# mainBoard.net
KiCad netlist of a schematic drawn in EAGLE
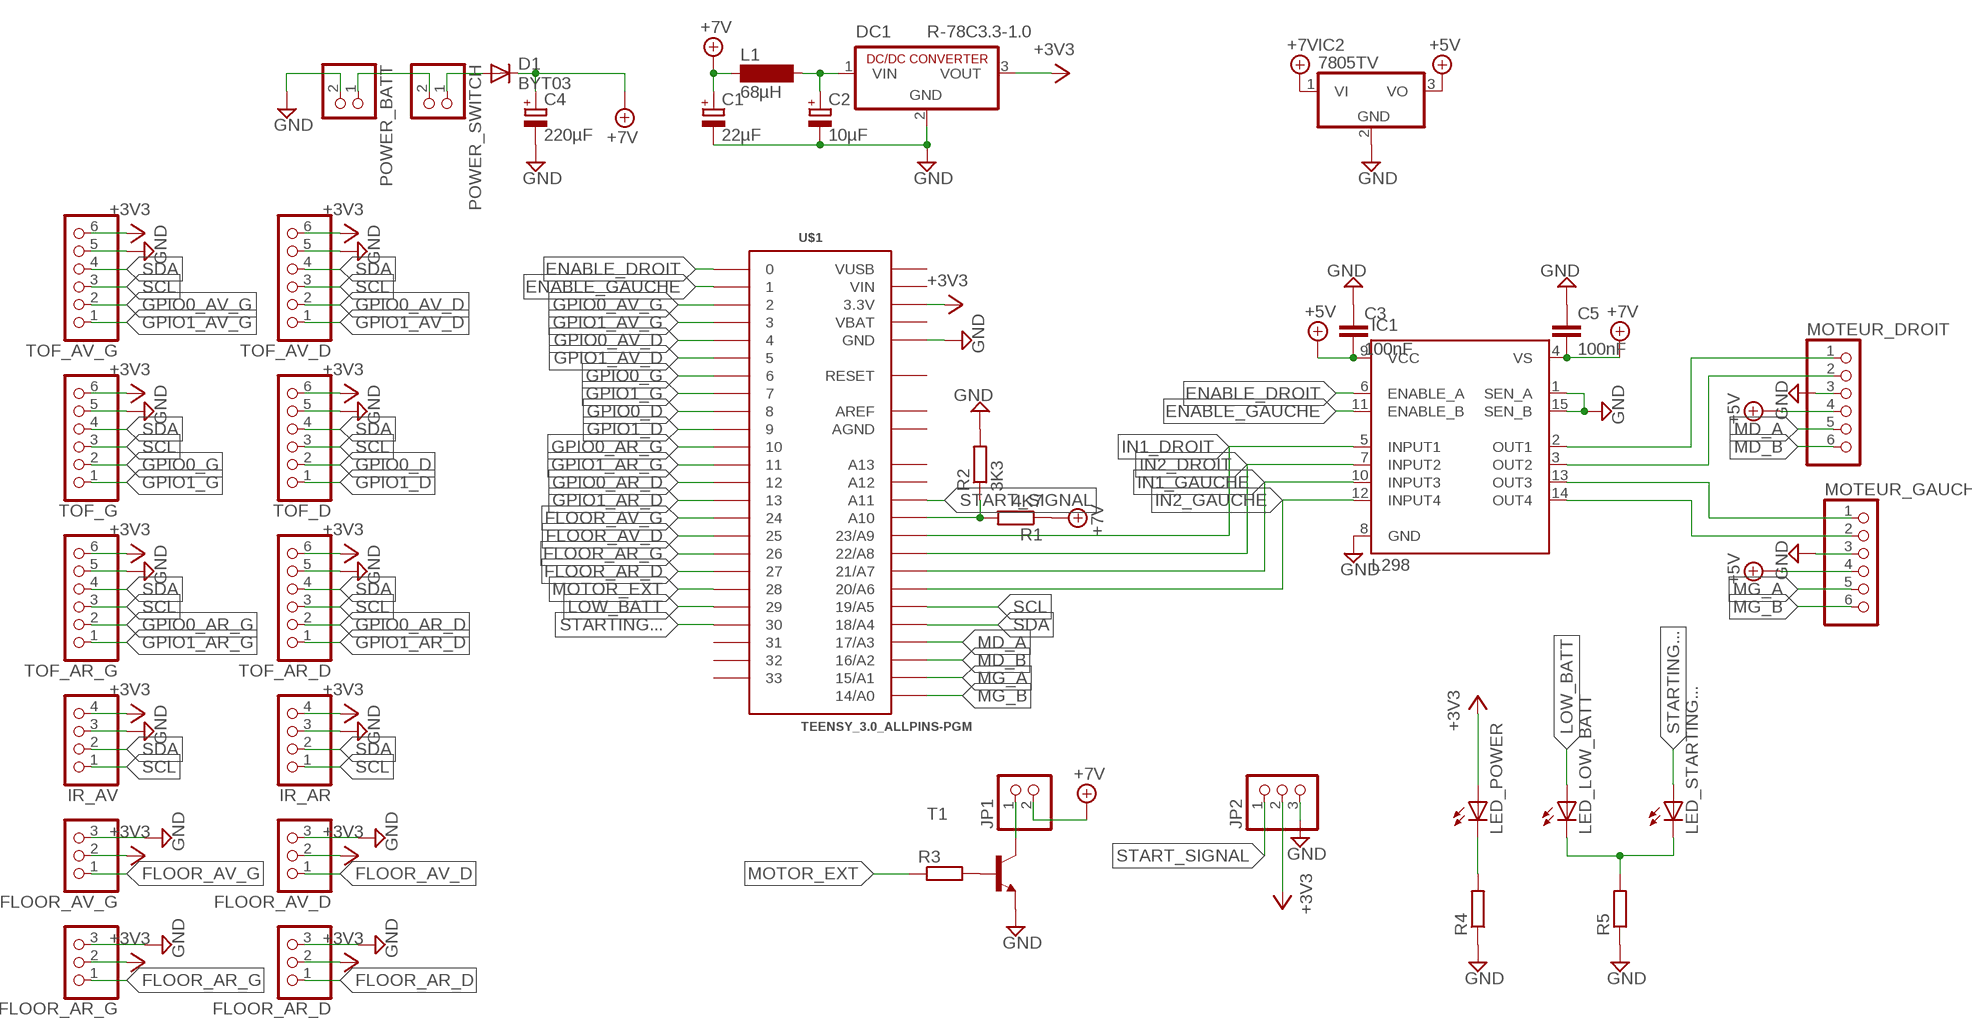
[diagram p0: schematic, sheet 1]

(export (version "E")
  (design (tool "Eeschema 10.0.6"))
  (components
    (comp (ref "C1")
      (value "22µF")
      (footprint "eagle-import:E2,5-6E")
      (libsource (lib "eagle-import") (part "CPOL-EUE2,5-6E"))
    )
    (comp (ref "C2")
      (value "10µF")
      (footprint "eagle-import:E2,5-6E")
      (libsource (lib "eagle-import") (part "CPOL-EUE2,5-6E"))
    )
    (comp (ref "C3")
      (value "100nF")
      (footprint "eagle-import:C050-024X044")
      (libsource (lib "eagle-import") (part "C-EU050-024X044"))
    )
    (comp (ref "C4")
      (value "220µF")
      (footprint "eagle-import:E2,5-7")
      (libsource (lib "eagle-import") (part "CPOL-EUE2.5-7"))
    )
    (comp (ref "C5")
      (value "100nF")
      (footprint "eagle-import:C050-024X044")
      (libsource (lib "eagle-import") (part "C-EU050-024X044"))
    )
    (comp (ref "D1")
      (value "BYT03")
      (footprint "eagle-import:DO27-15")
      (libsource (lib "eagle-import") (part "BYT03"))
    )
    (comp (ref "DC1")
      (value "R-78C3.3-1.0")
      (footprint "eagle-import:SIP3")
      (libsource (lib "eagle-import") (part "R-78C-1.03.3"))
    )
    (comp (ref "FLOOR_AR_D")
      (value "PINHD-1X3")
      (footprint "eagle-import:1X03")
      (libsource (lib "eagle-import") (part "PINHD-1X3"))
    )
    (comp (ref "FLOOR_AR_G")
      (value "PINHD-1X3")
      (footprint "eagle-import:1X03")
      (libsource (lib "eagle-import") (part "PINHD-1X3"))
    )
    (comp (ref "FLOOR_AV_D")
      (value "PINHD-1X3")
      (footprint "eagle-import:1X03")
      (libsource (lib "eagle-import") (part "PINHD-1X3"))
    )
    (comp (ref "FLOOR_AV_G")
      (value "PINHD-1X3")
      (footprint "eagle-import:1X03")
      (libsource (lib "eagle-import") (part "PINHD-1X3"))
    )
    (comp (ref "IC1")
      (value "L298")
      (footprint "eagle-import:MULTIWATT-15")
      (fields (field (name "MPN") "L298N"))
      (libsource (lib "eagle-import") (part "L298"))
    )
    (comp (ref "IC2")
      (value "7805TV")
      (footprint "eagle-import:TO220V")
      (libsource (lib "eagle-import") (part "78TV05"))
    )
    (comp (ref "IR_AR")
      (value "PINHD-1X4")
      (footprint "eagle-import:1X04")
      (libsource (lib "eagle-import") (part "PINHD-1X4"))
    )
    (comp (ref "IR_AV")
      (value "PINHD-1X4")
      (footprint "eagle-import:1X04")
      (libsource (lib "eagle-import") (part "PINHD-1X4"))
    )
    (comp (ref "JP1")
      (value "PINHD-1X2")
      (footprint "eagle-import:1X02")
      (libsource (lib "eagle-import") (part "PINHD-1X2"))
    )
    (comp (ref "JP2")
      (value "PINHD-1X3")
      (footprint "eagle-import:1X03")
      (libsource (lib "eagle-import") (part "PINHD-1X3"))
    )
    (comp (ref "L1")
      (value "68µH")
      (footprint "eagle-import:BS11")
      (libsource (lib "eagle-import") (part "BS11"))
    )
    (comp (ref "LED_LOW_BATT")
      (value "LED3MM")
      (footprint "eagle-import:LED3MM")
      (libsource (lib "eagle-import") (part "LED3MM"))
    )
    (comp (ref "LED_POWER")
      (value "LED3MM")
      (footprint "eagle-import:LED3MM")
      (libsource (lib "eagle-import") (part "LED3MM"))
    )
    (comp (ref "LED_STARTING...")
      (value "LED3MM")
      (footprint "eagle-import:LED3MM")
      (libsource (lib "eagle-import") (part "LED3MM"))
    )
    (comp (ref "MOTEUR_DROIT")
      (value "PINHD-1X6")
      (footprint "eagle-import:1X06")
      (libsource (lib "eagle-import") (part "PINHD-1X6"))
    )
    (comp (ref "MOTEUR_GAUCHE")
      (value "PINHD-1X6")
      (footprint "eagle-import:1X06")
      (libsource (lib "eagle-import") (part "PINHD-1X6"))
    )
    (comp (ref "POWER_BATT")
      (value "PINHD-1X2")
      (footprint "eagle-import:1X02")
      (libsource (lib "eagle-import") (part "PINHD-1X2"))
    )
    (comp (ref "POWER_SWITCH")
      (value "PINHD-1X2")
      (footprint "eagle-import:1X02")
      (libsource (lib "eagle-import") (part "PINHD-1X2"))
    )
    (comp (ref "R1")
      (value "4K7")
      (footprint "eagle-import:0204_7")
      (libsource (lib "eagle-import") (part "R-EU_0204/7"))
    )
    (comp (ref "R2")
      (value "3K3")
      (footprint "eagle-import:0204_7")
      (libsource (lib "eagle-import") (part "R-EU_0204/7"))
    )
    (comp (ref "R3")
      (value "R-EU_0204/7")
      (footprint "eagle-import:0204_7")
      (libsource (lib "eagle-import") (part "R-EU_0204/7"))
    )
    (comp (ref "R4")
      (value "R-EU_0204/7")
      (footprint "eagle-import:0204_7")
      (libsource (lib "eagle-import") (part "R-EU_0204/7"))
    )
    (comp (ref "R5")
      (value "R-EU_0207/2V")
      (footprint "eagle-import:0207_2V")
      (libsource (lib "eagle-import") (part "R-EU_0207/2V"))
    )
    (comp (ref "T1")
      (value "2N4124-NPN-TO92-CBE")
      (footprint "eagle-import:TO92-CBE")
      (libsource (lib "eagle-import") (part "-NPN-TO92-CBE2N4124"))
    )
    (comp (ref "TOF_AR_D")
      (value "PINHD-1X6")
      (footprint "eagle-import:1X06")
      (libsource (lib "eagle-import") (part "PINHD-1X6"))
    )
    (comp (ref "TOF_AR_G")
      (value "PINHD-1X6")
      (footprint "eagle-import:1X06")
      (libsource (lib "eagle-import") (part "PINHD-1X6"))
    )
    (comp (ref "TOF_AV_D")
      (value "PINHD-1X6")
      (footprint "eagle-import:1X06")
      (libsource (lib "eagle-import") (part "PINHD-1X6"))
    )
    (comp (ref "TOF_AV_G")
      (value "PINHD-1X6")
      (footprint "eagle-import:1X06")
      (libsource (lib "eagle-import") (part "PINHD-1X6"))
    )
    (comp (ref "TOF_D")
      (value "PINHD-1X6")
      (footprint "eagle-import:1X06")
      (libsource (lib "eagle-import") (part "PINHD-1X6"))
    )
    (comp (ref "TOF_G")
      (value "PINHD-1X6")
      (footprint "eagle-import:1X06")
      (libsource (lib "eagle-import") (part "PINHD-1X6"))
    )
    (comp (ref "U$1")
      (value "TEENSY_3.0_ALLPINS-PGM")
      (footprint "eagle-import:TEENSY_3.0_ALLPINS-PGM")
      (libsource (lib "eagle-import") (part "TEENSY_3.0_ALLPINS-PGM"))
    )
  )
  (nets
    (net (code "1") (name "+3V3") (class "Default")
      (node (ref "DC1") (pin "3") (pinfunction "VOUT_3") (pintype "passive"))
      (node (ref "FLOOR_AR_D") (pin "2") (pinfunction "2_2") (pintype "passive"))
      (node (ref "FLOOR_AR_G") (pin "2") (pinfunction "2_2") (pintype "passive"))
      (node (ref "FLOOR_AV_D") (pin "2") (pinfunction "2_2") (pintype "passive"))
      (node (ref "FLOOR_AV_G") (pin "2") (pinfunction "2_2") (pintype "passive"))
      (node (ref "IR_AR") (pin "4") (pinfunction "4_4") (pintype "passive"))
      (node (ref "IR_AV") (pin "4") (pinfunction "4_4") (pintype "passive"))
      (node (ref "JP2") (pin "2") (pinfunction "2_2") (pintype "passive"))
      (node (ref "LED_POWER") (pin "A") (pinfunction "A_A") (pintype "passive"))
      (node (ref "TOF_AR_D") (pin "6") (pinfunction "6_6") (pintype "passive"))
      (node (ref "TOF_AR_G") (pin "6") (pinfunction "6_6") (pintype "passive"))
      (node (ref "TOF_AV_D") (pin "6") (pinfunction "6_6") (pintype "passive"))
      (node (ref "TOF_AV_G") (pin "6") (pinfunction "6_6") (pintype "passive"))
      (node (ref "TOF_D") (pin "6") (pinfunction "6_6") (pintype "passive"))
      (node (ref "TOF_G") (pin "6") (pinfunction "6_6") (pintype "passive"))
      (node (ref "U$1") (pin "3.3V") (pinfunction "3.3V_3.3V") (pintype "power_in"))
      (node (ref "U$1") (pin "3.3V1") (pinfunction "3.3V_3.3V1") (pintype "power_in"))
      (node (ref "U$1") (pin "3.3V2") (pinfunction "3.3V_3.3V2") (pintype "power_in"))
    )
    (net (code "2") (name "+5V") (class "Default")
      (node (ref "C3") (pin "2") (pinfunction "2_2") (pintype "passive"))
      (node (ref "IC1") (pin "9") (pinfunction "VCC_9") (pintype "power_in"))
      (node (ref "IC2") (pin "3") (pinfunction "VO_3") (pintype "passive"))
      (node (ref "MOTEUR_DROIT") (pin "4") (pinfunction "4_4") (pintype "passive"))
      (node (ref "MOTEUR_GAUCHE") (pin "4") (pinfunction "4_4") (pintype "passive"))
    )
    (net (code "3") (name "+7V") (class "Default")
      (node (ref "C1") (pin "+") (pinfunction "+_+") (pintype "passive"))
      (node (ref "C4") (pin "+") (pinfunction "+_+") (pintype "passive"))
      (node (ref "C5") (pin "2") (pinfunction "2_2") (pintype "passive"))
      (node (ref "D1") (pin "C") (pinfunction "C_C") (pintype "passive"))
      (node (ref "IC1") (pin "4") (pinfunction "VS_4") (pintype "power_in"))
      (node (ref "IC2") (pin "1") (pinfunction "VI_1") (pintype "input"))
      (node (ref "JP1") (pin "2") (pinfunction "2_2") (pintype "passive"))
      (node (ref "L1") (pin "1") (pinfunction "1_1") (pintype "passive"))
      (node (ref "R1") (pin "1") (pinfunction "1_1") (pintype "passive"))
    )
    (net (code "4") (name "/AGND") (class "Default")
      (node (ref "U$1") (pin "AGND") (pinfunction "AGND_AGND") (pintype "power_in"))
    )
    (net (code "5") (name "/AREF") (class "Default")
      (node (ref "U$1") (pin "AREF") (pinfunction "AREF_AREF") (pintype "power_in"))
    )
    (net (code "6") (name "/VBAT") (class "Default")
      (node (ref "U$1") (pin "VBAT") (pinfunction "VBAT_VBAT") (pintype "power_in"))
    )
    (net (code "7") (name "/VIN") (class "Default")
      (node (ref "U$1") (pin "VIN") (pinfunction "VIN_VIN") (pintype "power_in"))
    )
    (net (code "8") (name "/VUSB") (class "Default")
      (node (ref "U$1") (pin "VUSB") (pinfunction "VUSB_VUSB") (pintype "power_in"))
    )
    (net (code "9") (name "ENABLE_DROIT") (class "Default")
      (node (ref "IC1") (pin "6") (pinfunction "ENABLE_A_6") (pintype "input"))
      (node (ref "U$1") (pin "0") (pinfunction "0_0") (pintype "bidirectional"))
    )
    (net (code "10") (name "ENABLE_GAUCHE") (class "Default")
      (node (ref "IC1") (pin "11") (pinfunction "ENABLE_B_11") (pintype "input"))
      (node (ref "U$1") (pin "1") (pinfunction "1_1") (pintype "bidirectional"))
    )
    (net (code "11") (name "FLOOR_AR_D") (class "Default")
      (node (ref "FLOOR_AR_D") (pin "1") (pinfunction "1_1") (pintype "passive"))
      (node (ref "U$1") (pin "27") (pinfunction "27_27") (pintype "bidirectional"))
    )
    (net (code "12") (name "FLOOR_AR_G") (class "Default")
      (node (ref "FLOOR_AR_G") (pin "1") (pinfunction "1_1") (pintype "passive"))
      (node (ref "U$1") (pin "26") (pinfunction "26_26") (pintype "bidirectional"))
    )
    (net (code "13") (name "FLOOR_AV_D") (class "Default")
      (node (ref "FLOOR_AV_D") (pin "1") (pinfunction "1_1") (pintype "passive"))
      (node (ref "U$1") (pin "25") (pinfunction "25_25") (pintype "bidirectional"))
    )
    (net (code "14") (name "FLOOR_AV_G") (class "Default")
      (node (ref "FLOOR_AV_G") (pin "1") (pinfunction "1_1") (pintype "passive"))
      (node (ref "U$1") (pin "24") (pinfunction "24_24") (pintype "bidirectional"))
    )
    (net (code "15") (name "GND") (class "Default")
      (node (ref "C1") (pin "-") (pinfunction "-_-") (pintype "passive"))
      (node (ref "C2") (pin "-") (pinfunction "-_-") (pintype "passive"))
      (node (ref "C3") (pin "1") (pinfunction "1_1") (pintype "passive"))
      (node (ref "C4") (pin "-") (pinfunction "-_-") (pintype "passive"))
      (node (ref "C5") (pin "1") (pinfunction "1_1") (pintype "passive"))
      (node (ref "DC1") (pin "2") (pinfunction "GND_2") (pintype "passive"))
      (node (ref "FLOOR_AR_D") (pin "3") (pinfunction "3_3") (pintype "passive"))
      (node (ref "FLOOR_AR_G") (pin "3") (pinfunction "3_3") (pintype "passive"))
      (node (ref "FLOOR_AV_D") (pin "3") (pinfunction "3_3") (pintype "passive"))
      (node (ref "FLOOR_AV_G") (pin "3") (pinfunction "3_3") (pintype "passive"))
      (node (ref "IC1") (pin "1") (pinfunction "SEN_A_1") (pintype "input"))
      (node (ref "IC1") (pin "15") (pinfunction "SEN_B_15") (pintype "input"))
      (node (ref "IC1") (pin "8") (pinfunction "GND_8") (pintype "power_in"))
      (node (ref "IC2") (pin "2") (pinfunction "GND_2") (pintype "passive"))
      (node (ref "IR_AR") (pin "3") (pinfunction "3_3") (pintype "passive"))
      (node (ref "IR_AV") (pin "3") (pinfunction "3_3") (pintype "passive"))
      (node (ref "JP2") (pin "3") (pinfunction "3_3") (pintype "passive"))
      (node (ref "MOTEUR_DROIT") (pin "3") (pinfunction "3_3") (pintype "passive"))
      (node (ref "MOTEUR_GAUCHE") (pin "3") (pinfunction "3_3") (pintype "passive"))
      (node (ref "POWER_BATT") (pin "2") (pinfunction "2_2") (pintype "passive"))
      (node (ref "R2") (pin "2") (pinfunction "2_2") (pintype "passive"))
      (node (ref "R4") (pin "1") (pinfunction "1_1") (pintype "passive"))
      (node (ref "R5") (pin "1") (pinfunction "1_1") (pintype "passive"))
      (node (ref "T1") (pin "E") (pinfunction "E_E") (pintype "passive"))
      (node (ref "TOF_AR_D") (pin "5") (pinfunction "5_5") (pintype "passive"))
      (node (ref "TOF_AR_G") (pin "5") (pinfunction "5_5") (pintype "passive"))
      (node (ref "TOF_AV_D") (pin "5") (pinfunction "5_5") (pintype "passive"))
      (node (ref "TOF_AV_G") (pin "5") (pinfunction "5_5") (pintype "passive"))
      (node (ref "TOF_D") (pin "5") (pinfunction "5_5") (pintype "passive"))
      (node (ref "TOF_G") (pin "5") (pinfunction "5_5") (pintype "passive"))
      (node (ref "U$1") (pin "GND") (pinfunction "GND_GND") (pintype "power_in"))
      (node (ref "U$1") (pin "GND1") (pinfunction "GND_GND1") (pintype "power_in"))
      (node (ref "U$1") (pin "GND2") (pinfunction "GND_GND2") (pintype "power_in"))
    )
    (net (code "16") (name "GPIO0_AR_D") (class "Default")
      (node (ref "TOF_AR_D") (pin "2") (pinfunction "2_2") (pintype "passive"))
      (node (ref "U$1") (pin "12") (pinfunction "12_12") (pintype "bidirectional"))
    )
    (net (code "17") (name "GPIO0_AR_G") (class "Default")
      (node (ref "TOF_AR_G") (pin "2") (pinfunction "2_2") (pintype "passive"))
      (node (ref "U$1") (pin "10") (pinfunction "10_10") (pintype "bidirectional"))
    )
    (net (code "18") (name "GPIO0_AV_D") (class "Default")
      (node (ref "TOF_AV_D") (pin "2") (pinfunction "2_2") (pintype "passive"))
      (node (ref "U$1") (pin "4") (pinfunction "4_4") (pintype "bidirectional"))
    )
    (net (code "19") (name "GPIO0_AV_G") (class "Default")
      (node (ref "TOF_AV_G") (pin "2") (pinfunction "2_2") (pintype "passive"))
      (node (ref "U$1") (pin "2") (pinfunction "2_2") (pintype "bidirectional"))
    )
    (net (code "20") (name "GPIO0_D") (class "Default")
      (node (ref "TOF_D") (pin "2") (pinfunction "2_2") (pintype "passive"))
      (node (ref "U$1") (pin "8") (pinfunction "8_8") (pintype "bidirectional"))
    )
    (net (code "21") (name "GPIO0_G") (class "Default")
      (node (ref "TOF_G") (pin "2") (pinfunction "2_2") (pintype "passive"))
      (node (ref "U$1") (pin "6") (pinfunction "6_6") (pintype "bidirectional"))
    )
    (net (code "22") (name "GPIO1_AR_D") (class "Default")
      (node (ref "TOF_AR_D") (pin "1") (pinfunction "1_1") (pintype "passive"))
      (node (ref "U$1") (pin "13") (pinfunction "13_13") (pintype "bidirectional"))
    )
    (net (code "23") (name "GPIO1_AR_G") (class "Default")
      (node (ref "TOF_AR_G") (pin "1") (pinfunction "1_1") (pintype "passive"))
      (node (ref "U$1") (pin "11") (pinfunction "11_11") (pintype "bidirectional"))
    )
    (net (code "24") (name "GPIO1_AV_D") (class "Default")
      (node (ref "TOF_AV_D") (pin "1") (pinfunction "1_1") (pintype "passive"))
      (node (ref "U$1") (pin "5") (pinfunction "5_5") (pintype "bidirectional"))
    )
    (net (code "25") (name "GPIO1_AV_G") (class "Default")
      (node (ref "TOF_AV_G") (pin "1") (pinfunction "1_1") (pintype "passive"))
      (node (ref "U$1") (pin "3") (pinfunction "3_3") (pintype "bidirectional"))
    )
    (net (code "26") (name "GPIO1_D") (class "Default")
      (node (ref "TOF_D") (pin "1") (pinfunction "1_1") (pintype "passive"))
      (node (ref "U$1") (pin "9") (pinfunction "9_9") (pintype "bidirectional"))
    )
    (net (code "27") (name "GPIO1_G") (class "Default")
      (node (ref "TOF_G") (pin "1") (pinfunction "1_1") (pintype "passive"))
      (node (ref "U$1") (pin "7") (pinfunction "7_7") (pintype "bidirectional"))
    )
    (net (code "28") (name "IN1_DROIT") (class "Default")
      (node (ref "IC1") (pin "5") (pinfunction "INPUT1_5") (pintype "input"))
      (node (ref "U$1") (pin "23/A9") (pinfunction "23/A9_23/A9") (pintype "bidirectional"))
    )
    (net (code "29") (name "IN1_GAUCHE") (class "Default")
      (node (ref "IC1") (pin "10") (pinfunction "INPUT3_10") (pintype "input"))
      (node (ref "U$1") (pin "21/A7") (pinfunction "21/A7_21/A7") (pintype "bidirectional"))
    )
    (net (code "30") (name "IN2_DROIT") (class "Default")
      (node (ref "IC1") (pin "7") (pinfunction "INPUT2_7") (pintype "input"))
      (node (ref "U$1") (pin "22/A8") (pinfunction "22/A8_22/A8") (pintype "bidirectional"))
    )
    (net (code "31") (name "IN2_GAUCHE") (class "Default")
      (node (ref "IC1") (pin "12") (pinfunction "INPUT4_12") (pintype "input"))
      (node (ref "U$1") (pin "20/A6") (pinfunction "20/A6_20/A6") (pintype "bidirectional"))
    )
    (net (code "32") (name "LOW_BATT") (class "Default")
      (node (ref "LED_LOW_BATT") (pin "A") (pinfunction "A_A") (pintype "passive"))
      (node (ref "U$1") (pin "29") (pinfunction "29_29") (pintype "bidirectional"))
    )
    (net (code "33") (name "MD_A") (class "Default")
      (node (ref "MOTEUR_DROIT") (pin "5") (pinfunction "5_5") (pintype "passive"))
      (node (ref "U$1") (pin "17/A3") (pinfunction "17/A3_17/A3") (pintype "bidirectional"))
    )
    (net (code "34") (name "MD_B") (class "Default")
      (node (ref "MOTEUR_DROIT") (pin "6") (pinfunction "6_6") (pintype "passive"))
      (node (ref "U$1") (pin "16/A2") (pinfunction "16/A2_16/A2") (pintype "bidirectional"))
    )
    (net (code "35") (name "MG_A") (class "Default")
      (node (ref "MOTEUR_GAUCHE") (pin "5") (pinfunction "5_5") (pintype "passive"))
      (node (ref "U$1") (pin "15/A1") (pinfunction "15/A1_15/A1") (pintype "bidirectional"))
    )
    (net (code "36") (name "MG_B") (class "Default")
      (node (ref "MOTEUR_GAUCHE") (pin "6") (pinfunction "6_6") (pintype "passive"))
      (node (ref "U$1") (pin "14/A0") (pinfunction "14/A0_14/A0") (pintype "bidirectional"))
    )
    (net (code "37") (name "MOTOR_EXT") (class "Default")
      (node (ref "R3") (pin "1") (pinfunction "1_1") (pintype "passive"))
      (node (ref "U$1") (pin "28") (pinfunction "28_28") (pintype "bidirectional"))
    )
    (net (code "38") (name "Net-(D1-PadA)") (class "Default")
      (node (ref "D1") (pin "A") (pinfunction "A_A") (pintype "passive"))
      (node (ref "POWER_SWITCH") (pin "1") (pinfunction "1_1") (pintype "passive"))
    )
    (net (code "39") (name "Net-(DC1-VIN)") (class "Default")
      (node (ref "C2") (pin "+") (pinfunction "+_+") (pintype "passive"))
      (node (ref "DC1") (pin "1") (pinfunction "VIN_1") (pintype "passive"))
      (node (ref "L1") (pin "2") (pinfunction "2_2") (pintype "passive"))
    )
    (net (code "40") (name "Net-(IC1-OUT1)") (class "Default")
      (node (ref "IC1") (pin "2") (pinfunction "OUT1_2") (pintype "output"))
      (node (ref "MOTEUR_DROIT") (pin "1") (pinfunction "1_1") (pintype "passive"))
    )
    (net (code "41") (name "Net-(IC1-OUT2)") (class "Default")
      (node (ref "IC1") (pin "3") (pinfunction "OUT2_3") (pintype "output"))
      (node (ref "MOTEUR_DROIT") (pin "2") (pinfunction "2_2") (pintype "passive"))
    )
    (net (code "42") (name "Net-(IC1-OUT3)") (class "Default")
      (node (ref "IC1") (pin "13") (pinfunction "OUT3_13") (pintype "output"))
      (node (ref "MOTEUR_GAUCHE") (pin "1") (pinfunction "1_1") (pintype "passive"))
    )
    (net (code "43") (name "Net-(IC1-OUT4)") (class "Default")
      (node (ref "IC1") (pin "14") (pinfunction "OUT4_14") (pintype "output"))
      (node (ref "MOTEUR_GAUCHE") (pin "2") (pinfunction "2_2") (pintype "passive"))
    )
    (net (code "44") (name "Net-(JP1-Pad1)") (class "Default")
      (node (ref "JP1") (pin "1") (pinfunction "1_1") (pintype "passive"))
      (node (ref "T1") (pin "C") (pinfunction "C_C") (pintype "passive"))
    )
    (net (code "45") (name "Net-(LED_LOW_BATT-C)") (class "Default")
      (node (ref "LED_LOW_BATT") (pin "K") (pinfunction "C_K") (pintype "passive"))
      (node (ref "LED_STARTING...") (pin "K") (pinfunction "C_K") (pintype "passive"))
      (node (ref "R5") (pin "2") (pinfunction "2_2") (pintype "passive"))
    )
    (net (code "46") (name "Net-(LED_POWER-C)") (class "Default")
      (node (ref "LED_POWER") (pin "K") (pinfunction "C_K") (pintype "passive"))
      (node (ref "R4") (pin "2") (pinfunction "2_2") (pintype "passive"))
    )
    (net (code "47") (name "Net-(POWER_BATT-Pad1)") (class "Default")
      (node (ref "POWER_BATT") (pin "1") (pinfunction "1_1") (pintype "passive"))
      (node (ref "POWER_SWITCH") (pin "2") (pinfunction "2_2") (pintype "passive"))
    )
    (net (code "48") (name "Net-(R1-Pad2)") (class "Default")
      (node (ref "R1") (pin "2") (pinfunction "2_2") (pintype "passive"))
      (node (ref "R2") (pin "1") (pinfunction "1_1") (pintype "passive"))
      (node (ref "U$1") (pin "A10") (pinfunction "A10_A10") (pintype "bidirectional"))
    )
    (net (code "49") (name "Net-(R3-Pad2)") (class "Default")
      (node (ref "R3") (pin "2") (pinfunction "2_2") (pintype "passive"))
      (node (ref "T1") (pin "B") (pinfunction "B_B") (pintype "passive"))
    )
    (net (code "50") (name "SCL") (class "Default")
      (node (ref "IR_AR") (pin "1") (pinfunction "1_1") (pintype "passive"))
      (node (ref "IR_AV") (pin "1") (pinfunction "1_1") (pintype "passive"))
      (node (ref "TOF_AR_D") (pin "3") (pinfunction "3_3") (pintype "passive"))
      (node (ref "TOF_AR_G") (pin "3") (pinfunction "3_3") (pintype "passive"))
      (node (ref "TOF_AV_D") (pin "3") (pinfunction "3_3") (pintype "passive"))
      (node (ref "TOF_AV_G") (pin "3") (pinfunction "3_3") (pintype "passive"))
      (node (ref "TOF_D") (pin "3") (pinfunction "3_3") (pintype "passive"))
      (node (ref "TOF_G") (pin "3") (pinfunction "3_3") (pintype "passive"))
      (node (ref "U$1") (pin "19/A5") (pinfunction "19/A5_19/A5") (pintype "bidirectional"))
    )
    (net (code "51") (name "SDA") (class "Default")
      (node (ref "IR_AR") (pin "2") (pinfunction "2_2") (pintype "passive"))
      (node (ref "IR_AV") (pin "2") (pinfunction "2_2") (pintype "passive"))
      (node (ref "TOF_AR_D") (pin "4") (pinfunction "4_4") (pintype "passive"))
      (node (ref "TOF_AR_G") (pin "4") (pinfunction "4_4") (pintype "passive"))
      (node (ref "TOF_AV_D") (pin "4") (pinfunction "4_4") (pintype "passive"))
      (node (ref "TOF_AV_G") (pin "4") (pinfunction "4_4") (pintype "passive"))
      (node (ref "TOF_D") (pin "4") (pinfunction "4_4") (pintype "passive"))
      (node (ref "TOF_G") (pin "4") (pinfunction "4_4") (pintype "passive"))
      (node (ref "U$1") (pin "18/A4") (pinfunction "18/A4_18/A4") (pintype "bidirectional"))
    )
    (net (code "52") (name "STARTING...") (class "Default")
      (node (ref "LED_STARTING...") (pin "A") (pinfunction "A_A") (pintype "passive"))
      (node (ref "U$1") (pin "30") (pinfunction "30_30") (pintype "bidirectional"))
    )
    (net (code "53") (name "START_SIGNAL") (class "Default")
      (node (ref "JP2") (pin "1") (pinfunction "1_1") (pintype "passive"))
      (node (ref "U$1") (pin "A11") (pinfunction "A11_A11") (pintype "bidirectional"))
    )
    (net (code "54") (name "unconnected-(U$1-Pad31)") (class "Default")
      (node (ref "U$1") (pin "31") (pinfunction "31_31") (pintype "bidirectional"))
    )
    (net (code "55") (name "unconnected-(U$1-Pad32)") (class "Default")
      (node (ref "U$1") (pin "32") (pinfunction "32_32") (pintype "bidirectional"))
    )
    (net (code "56") (name "unconnected-(U$1-Pad33)") (class "Default")
      (node (ref "U$1") (pin "33") (pinfunction "33_33") (pintype "bidirectional"))
    )
    (net (code "57") (name "unconnected-(U$1-PadA12)") (class "Default")
      (node (ref "U$1") (pin "A12") (pinfunction "A12_A12") (pintype "bidirectional"))
    )
    (net (code "58") (name "unconnected-(U$1-PadA13)") (class "Default")
      (node (ref "U$1") (pin "A13") (pinfunction "A13_A13") (pintype "bidirectional"))
    )
    (net (code "59") (name "unconnected-(U$1-RESET-PadRST)") (class "Default")
      (node (ref "U$1") (pin "RST") (pinfunction "RESET_RST") (pintype "bidirectional"))
    )
  )
)
